# HandPcb.net
KiCad netlist of a schematic drawn in Altium Designer
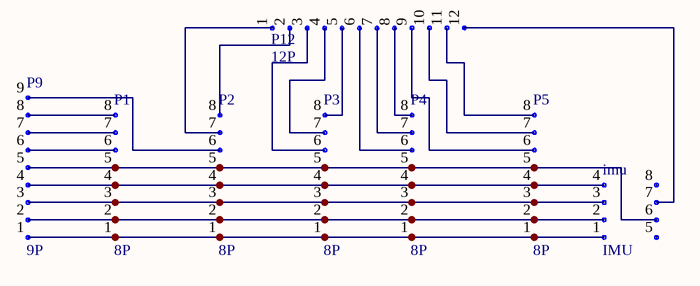
[diagram p0: HandPcb.SchDoc]

(export (version "E")
  (design (tool "Eeschema 10.0.6"))
  (components
    (comp (ref "imu") (value "IMU") (footprint "MPU9250") (libsource (lib "IMU") (part "IMU")))
    (comp (ref "P1") (value "8P") (footprint "8P") (libsource (lib "IMU") (part "8P")))
    (comp (ref "P2") (value "8P") (footprint "8P") (libsource (lib "IMU") (part "8P")))
    (comp (ref "P3") (value "8P") (footprint "8P") (libsource (lib "IMU") (part "8P")))
    (comp (ref "P4") (value "8P") (footprint "8P") (libsource (lib "IMU") (part "8P")))
    (comp (ref "P5") (value "8P") (footprint "8P") (libsource (lib "IMU") (part "8P")))
    (comp (ref "P9") (value "9P") (footprint "9p") (libsource (lib "IMU") (part "9P")))
    (comp (ref "P12") (value "12P") (footprint "12P") (libsource (lib "IMU") (part "12P")))
  )
  (nets
    (net (code "1") (name "Net-(P1-Pad1)") (class "Default")
      (node (ref "P1") (pin "1") (pinfunction "1_1") (pintype "passive"))
      (node (ref "P2") (pin "1") (pinfunction "1_1") (pintype "passive"))
      (node (ref "P3") (pin "1") (pinfunction "1_1") (pintype "passive"))
      (node (ref "P4") (pin "1") (pinfunction "1_1") (pintype "passive"))
      (node (ref "P5") (pin "1") (pinfunction "1_1") (pintype "passive"))
      (node (ref "P9") (pin "1") (pinfunction "1_1") (pintype "passive"))
      (node (ref "imu") (pin "1") (pinfunction "1_1") (pintype "passive"))
    )
    (net (code "2") (name "Net-(P1-Pad2)") (class "Default")
      (node (ref "P1") (pin "2") (pinfunction "2_2") (pintype "passive"))
      (node (ref "P2") (pin "2") (pinfunction "2_2") (pintype "passive"))
      (node (ref "P3") (pin "2") (pinfunction "2_2") (pintype "passive"))
      (node (ref "P4") (pin "2") (pinfunction "2_2") (pintype "passive"))
      (node (ref "P5") (pin "2") (pinfunction "2_2") (pintype "passive"))
      (node (ref "P9") (pin "2") (pinfunction "2_2") (pintype "passive"))
      (node (ref "imu") (pin "2") (pinfunction "2_2") (pintype "passive"))
    )
    (net (code "3") (name "Net-(P1-Pad3)") (class "Default")
      (node (ref "P1") (pin "3") (pinfunction "3_3") (pintype "passive"))
      (node (ref "P2") (pin "3") (pinfunction "3_3") (pintype "passive"))
      (node (ref "P3") (pin "3") (pinfunction "3_3") (pintype "passive"))
      (node (ref "P4") (pin "3") (pinfunction "3_3") (pintype "passive"))
      (node (ref "P5") (pin "3") (pinfunction "3_3") (pintype "passive"))
      (node (ref "P9") (pin "3") (pinfunction "3_3") (pintype "passive"))
      (node (ref "imu") (pin "3") (pinfunction "3_3") (pintype "passive"))
    )
    (net (code "4") (name "Net-(P1-Pad4)") (class "Default")
      (node (ref "P1") (pin "4") (pinfunction "4_4") (pintype "passive"))
      (node (ref "P2") (pin "4") (pinfunction "4_4") (pintype "passive"))
      (node (ref "P3") (pin "4") (pinfunction "4_4") (pintype "passive"))
      (node (ref "P4") (pin "4") (pinfunction "4_4") (pintype "passive"))
      (node (ref "P5") (pin "4") (pinfunction "4_4") (pintype "passive"))
      (node (ref "P9") (pin "4") (pinfunction "4_4") (pintype "passive"))
      (node (ref "imu") (pin "4") (pinfunction "4_4") (pintype "passive"))
    )
    (net (code "5") (name "Net-(P1-Pad5)") (class "Default")
      (node (ref "P1") (pin "5") (pinfunction "5_5") (pintype "passive"))
      (node (ref "P2") (pin "5") (pinfunction "5_5") (pintype "passive"))
      (node (ref "P3") (pin "5") (pinfunction "5_5") (pintype "passive"))
      (node (ref "P4") (pin "5") (pinfunction "5_5") (pintype "passive"))
      (node (ref "P5") (pin "5") (pinfunction "5_5") (pintype "passive"))
      (node (ref "P9") (pin "5") (pinfunction "5_5") (pintype "passive"))
      (node (ref "imu") (pin "6") (pinfunction "6_6") (pintype "passive"))
    )
    (net (code "6") (name "Net-(P1-Pad6)") (class "Default")
      (node (ref "P1") (pin "6") (pinfunction "6_6") (pintype "passive"))
      (node (ref "P9") (pin "6") (pinfunction "6_6") (pintype "passive"))
    )
    (net (code "7") (name "Net-(P1-Pad7)") (class "Default")
      (node (ref "P1") (pin "7") (pinfunction "7_7") (pintype "passive"))
      (node (ref "P9") (pin "7") (pinfunction "7_7") (pintype "passive"))
    )
    (net (code "8") (name "Net-(P1-Pad8)") (class "Default")
      (node (ref "P1") (pin "8") (pinfunction "8_8") (pintype "passive"))
      (node (ref "P9") (pin "8") (pinfunction "8_8") (pintype "passive"))
    )
    (net (code "9") (name "Net-(P2-Pad6)") (class "Default")
      (node (ref "P2") (pin "6") (pinfunction "6_6") (pintype "passive"))
      (node (ref "P9") (pin "9") (pinfunction "9_9") (pintype "passive"))
    )
    (net (code "10") (name "Net-(P12-Pad1)") (class "Default")
      (node (ref "P12") (pin "1") (pinfunction "1_1") (pintype "passive"))
      (node (ref "P2") (pin "7") (pinfunction "7_7") (pintype "passive"))
    )
    (net (code "11") (name "Net-(P12-Pad2)") (class "Default")
      (node (ref "P12") (pin "2") (pinfunction "2_2") (pintype "passive"))
      (node (ref "P2") (pin "8") (pinfunction "8_8") (pintype "passive"))
    )
    (net (code "12") (name "Net-(P12-Pad3)") (class "Default")
      (node (ref "P12") (pin "3") (pinfunction "3_3") (pintype "passive"))
      (node (ref "P3") (pin "6") (pinfunction "6_6") (pintype "passive"))
    )
    (net (code "13") (name "Net-(P12-Pad4)") (class "Default")
      (node (ref "P12") (pin "4") (pinfunction "4_4") (pintype "passive"))
      (node (ref "P3") (pin "7") (pinfunction "7_7") (pintype "passive"))
    )
    (net (code "14") (name "Net-(P12-Pad5)") (class "Default")
      (node (ref "P12") (pin "5") (pinfunction "5_5") (pintype "passive"))
      (node (ref "P3") (pin "8") (pinfunction "8_8") (pintype "passive"))
    )
    (net (code "15") (name "Net-(P12-Pad6)") (class "Default")
      (node (ref "P12") (pin "6") (pinfunction "6_6") (pintype "passive"))
      (node (ref "P4") (pin "6") (pinfunction "6_6") (pintype "passive"))
    )
    (net (code "16") (name "Net-(P12-Pad7)") (class "Default")
      (node (ref "P12") (pin "7") (pinfunction "7_7") (pintype "passive"))
      (node (ref "P4") (pin "7") (pinfunction "7_7") (pintype "passive"))
    )
    (net (code "17") (name "Net-(P12-Pad8)") (class "Default")
      (node (ref "P12") (pin "8") (pinfunction "8_8") (pintype "passive"))
      (node (ref "P4") (pin "8") (pinfunction "8_8") (pintype "passive"))
    )
    (net (code "18") (name "Net-(P12-Pad9)") (class "Default")
      (node (ref "P12") (pin "9") (pinfunction "9_9") (pintype "passive"))
      (node (ref "P5") (pin "6") (pinfunction "6_6") (pintype "passive"))
    )
    (net (code "19") (name "Net-(P12-Pad10)") (class "Default")
      (node (ref "P12") (pin "10") (pinfunction "10_10") (pintype "passive"))
      (node (ref "P5") (pin "7") (pinfunction "7_7") (pintype "passive"))
    )
    (net (code "20") (name "Net-(P12-Pad11)") (class "Default")
      (node (ref "P12") (pin "11") (pinfunction "11_11") (pintype "passive"))
      (node (ref "P5") (pin "8") (pinfunction "8_8") (pintype "passive"))
    )
    (net (code "21") (name "Net-(P12-Pad12)") (class "Default")
      (node (ref "P12") (pin "12") (pinfunction "12_12") (pintype "passive"))
      (node (ref "imu") (pin "7") (pinfunction "7_7") (pintype "passive"))
    )
    (net (code "22") (name "unconnected-(imu-Pad5)") (class "Default")
      (node (ref "imu") (pin "5") (pinfunction "5_5") (pintype "passive"))
    )
    (net (code "23") (name "unconnected-(imu-Pad8)") (class "Default")
      (node (ref "imu") (pin "8") (pinfunction "8_8") (pintype "passive"))
    )
  )
)
